# ZUM_Junior.net
KiCad netlist of a schematic drawn in Altium Designer
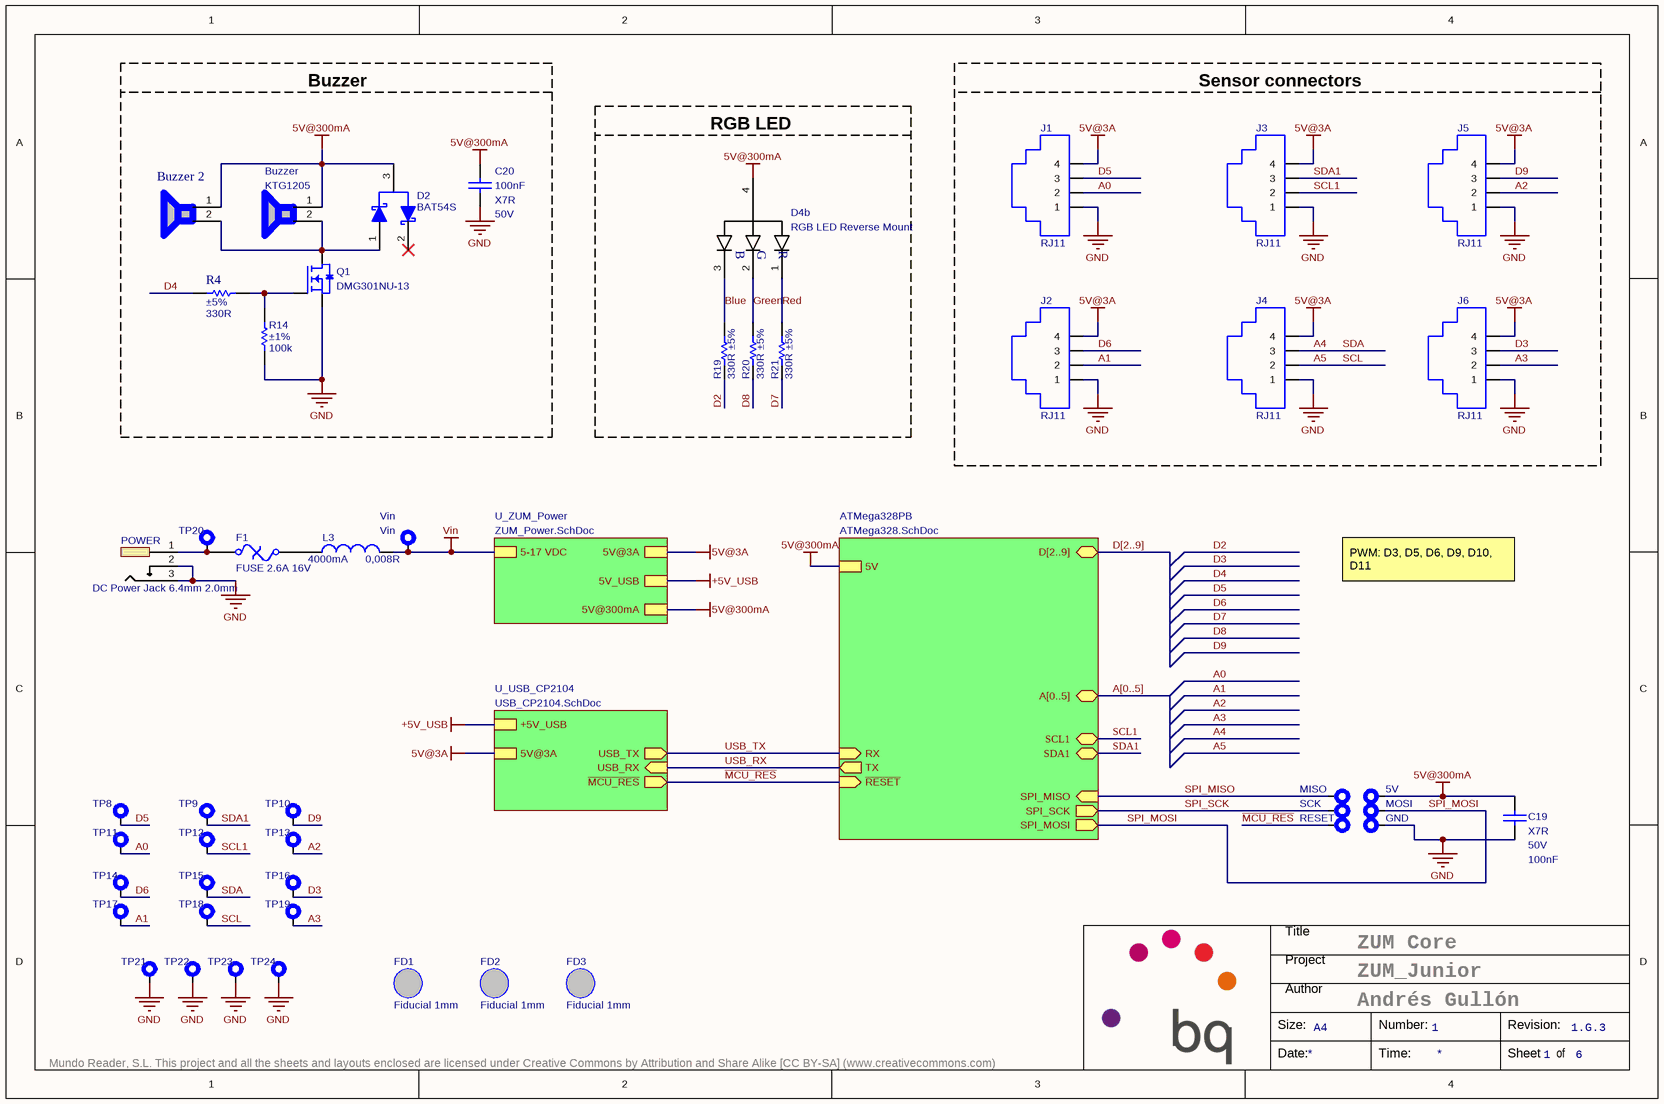
[diagram p0: ZUM_Junior.SchDoc]

(export (version "E")
  (design (tool "Eeschema 10.0.6"))
  (components
    (comp (ref "Buzzer")
      (value "KTG1205")
      (footprint "BUZZER SMD 13mm")
      (description "Buzzer")
      (fields (field (name "MANUFACTURER") "Kingstate Elect."))
      (libsource (lib "BQ Vault") (part "CMP-00356-1"))
    )
    (comp (ref "Buzzer 2")
      (value "Buzzer 8.5mm SMD")
      (footprint "YX-8014S05-2.7")
      (fields (field (name "MANUFACTURER") "Qinlon") (field (name "PART NUMBER") "YX-8014S-05"))
      (libsource (lib "BQ Vault") (part "BUZZER"))
    )
    (comp (ref "C19")
      (value "C0603_100nF_50V_±10%_X7R")
      (footprint "C0603")
      (fields
        (field (name "DIELECTRIC") "X7R")
        (field (name "VOLTAGE") "50V")
        (field (name "CAPACITANCE") "100nF")
        (field (name "MANUFACTURER") "Kemet")
        (field (name "TOLERANCE") "±10%")
      )
      (libsource (lib "BQ Vault") (part "CMP-00257-1"))
    )
    (comp (ref "C20")
      (value "C0603_100nF_50V_±10%_X7R")
      (footprint "C0603")
      (fields
        (field (name "DIELECTRIC") "X7R")
        (field (name "VOLTAGE") "50V")
        (field (name "CAPACITANCE") "100nF")
        (field (name "MANUFACTURER") "Kemet")
        (field (name "TOLERANCE") "±10%")
      )
      (libsource (lib "BQ Vault") (part "CMP-00257-1"))
    )
    (comp (ref "D2")
      (value "BAT54S")
      (footprint "SOT23-3")
      (description "Schottky Diode")
      (fields (field (name "MANUFACTURER") "NXP"))
      (libsource (lib "BQ Vault") (part "CMP-A2299-1"))
    )
    (comp (ref "D4b")
      (value "RGB LED Reverse Mount")
      (footprint "LED1205 Reverse")
      (fields (field (name "MANUFACTURER") "WÜrth Elektronik") (field (name "PART NUMBER") "RGB LED Reverse"))
      (libsource (lib "BQ Vault") (part "LED_RGB_2"))
    )
    (comp (ref "F1")
      (value "FUSE 2.6A 16V")
      (footprint "F1812")
      (description "Resettable Fuses")
      (fields (field (name "PART NUMBER") "FUSE 2.5A 16V") (field (name "VOLTAGE") "16V"))
      (libsource (lib "BQ Vault") (part "PTC_Fuse"))
    )
    (comp (ref "FD1")
      (value "Fiducial 1mm")
      (footprint "Fiducial_1mm")
      (description "Fiducial")
      (libsource (lib "BQ Vault") (part "Fiducial"))
    )
    (comp (ref "FD2")
      (value "Fiducial 1mm")
      (footprint "Fiducial_1mm")
      (description "Fiducial")
      (libsource (lib "BQ Vault") (part "Fiducial"))
    )
    (comp (ref "FD3")
      (value "Fiducial 1mm")
      (footprint "Fiducial_1mm")
      (description "Fiducial")
      (libsource (lib "BQ Vault") (part "Fiducial"))
    )
    (comp (ref "J1")
      (value "RJ11")
      (footprint "RJ11 SMD")
      (description "RJ11 4p4c SMD")
      (fields (field (name "MANUFACTURER") "Kycon"))
      (libsource (lib "BQ Vault") (part "RJ11"))
    )
    (comp (ref "J2")
      (value "RJ11")
      (footprint "RJ11 SMD")
      (description "RJ11 4p4c SMD")
      (fields (field (name "MANUFACTURER") "Kycon"))
      (libsource (lib "BQ Vault") (part "RJ11"))
    )
    (comp (ref "J3")
      (value "RJ11")
      (footprint "RJ11 SMD")
      (description "RJ11 4p4c SMD")
      (fields (field (name "MANUFACTURER") "Kycon"))
      (libsource (lib "BQ Vault") (part "RJ11"))
    )
    (comp (ref "J4")
      (value "RJ11")
      (footprint "RJ11 SMD")
      (description "RJ11 4p4c SMD")
      (fields (field (name "MANUFACTURER") "Kycon"))
      (libsource (lib "BQ Vault") (part "RJ11"))
    )
    (comp (ref "J5")
      (value "RJ11")
      (footprint "RJ11 SMD")
      (description "RJ11 4p4c SMD")
      (fields (field (name "MANUFACTURER") "Kycon"))
      (libsource (lib "BQ Vault") (part "RJ11"))
    )
    (comp (ref "J6")
      (value "RJ11")
      (footprint "RJ11 SMD")
      (description "RJ11 4p4c SMD")
      (fields (field (name "MANUFACTURER") "Kycon"))
      (libsource (lib "BQ Vault") (part "RJ11"))
    )
    (comp (ref "L3")
      (value "L0805_33R_0,008R_4000mA")
      (footprint "L0805")
      (fields
        (field (name "RESISTANCE_DC") "0,008R")
        (field (name "CURRENT") "4000mA")
        (field (name "MANUFACTURER") "Würth Elektronik")
      )
      (libsource (lib "BQ Vault") (part "CMP-A0714-1"))
    )
    (comp (ref "POWER")
      (value "DC Power Jack 6.4mm 2.0mm")
      (footprint "694106106102")
      (fields (field (name "MANUFACTURER") "Würth Elektronik") (field (name "PART NUMBER") "694106106102"))
      (libsource (lib "BQ Vault") (part "Power_Jack"))
    )
    (comp (ref "Q1")
      (value "DMG301NU-13")
      (footprint "SOT23-3")
      (description "N-MOSFET transistor")
      (fields (field (name "MANUFACTURER") "Diodes"))
      (libsource (lib "BQ Vault") (part "Mosfet_N"))
    )
    (comp (ref "R4")
      (value "R0402_330R_0.063W_±5%")
      (footprint "R0402")
      (fields
        (field (name "TOLERANCE") "±5%")
        (field (name "POWER") "0.063W")
        (field (name "RESISTANCE") "330R")
        (field (name "MANUFACTURER") "Vishay")
      )
      (libsource (lib "BQ Vault") (part "Resistor"))
    )
    (comp (ref "R14")
      (value "R0402_100k_0.063W_±1%")
      (footprint "R0402")
      (fields
        (field (name "TOLERANCE") "±1%")
        (field (name "POWER") "0.063W")
        (field (name "RESISTANCE") "100k")
        (field (name "MANUFACTURER") "Vishay")
      )
      (libsource (lib "BQ Vault") (part "CMP-A1835-2"))
    )
    (comp (ref "R19")
      (value "R0402_330R_0.063W_±5%")
      (footprint "R0402")
      (fields
        (field (name "TOLERANCE") "±5%")
        (field (name "POWER") "0.063W")
        (field (name "RESISTANCE") "330R")
        (field (name "MANUFACTURER") "Vishay")
      )
      (libsource (lib "BQ Vault") (part "Resistor"))
    )
    (comp (ref "R20")
      (value "R0402_330R_0.063W_±5%")
      (footprint "R0402")
      (fields
        (field (name "TOLERANCE") "±5%")
        (field (name "POWER") "0.063W")
        (field (name "RESISTANCE") "330R")
        (field (name "MANUFACTURER") "Vishay")
      )
      (libsource (lib "BQ Vault") (part "Resistor"))
    )
    (comp (ref "R21")
      (value "R0402_330R_0.063W_±5%")
      (footprint "R0402")
      (fields
        (field (name "TOLERANCE") "±5%")
        (field (name "POWER") "0.063W")
        (field (name "RESISTANCE") "330R")
        (field (name "MANUFACTURER") "Vishay")
      )
      (libsource (lib "BQ Vault") (part "Resistor"))
    )
    (comp (ref "TP8")
      (value "TP")
      (footprint "TP_POWER")
      (description "Testpoint 0.3mm")
      (fields (field (name "MANUFACTURER") "Oxley") (field (name "PART NUMBER") "TP_POWER"))
      (libsource (lib "BQ Vault") (part "CMP-A2499-3"))
    )
    (comp (ref "TP9")
      (value "TP")
      (footprint "TP_POWER")
      (description "Testpoint 0.3mm")
      (fields (field (name "MANUFACTURER") "Oxley") (field (name "PART NUMBER") "TP_POWER"))
      (libsource (lib "BQ Vault") (part "CMP-A2499-3"))
    )
    (comp (ref "TP10")
      (value "TP")
      (footprint "TP_POWER")
      (description "Testpoint 0.3mm")
      (fields (field (name "MANUFACTURER") "Oxley") (field (name "PART NUMBER") "TP_POWER"))
      (libsource (lib "BQ Vault") (part "CMP-A2499-3"))
    )
    (comp (ref "TP11")
      (value "TP")
      (footprint "TP_POWER")
      (description "Testpoint 0.3mm")
      (fields (field (name "MANUFACTURER") "Oxley") (field (name "PART NUMBER") "TP_POWER"))
      (libsource (lib "BQ Vault") (part "CMP-A2499-3"))
    )
    (comp (ref "TP12")
      (value "TP")
      (footprint "TP_POWER")
      (description "Testpoint 0.3mm")
      (fields (field (name "MANUFACTURER") "Oxley") (field (name "PART NUMBER") "TP_POWER"))
      (libsource (lib "BQ Vault") (part "CMP-A2499-3"))
    )
    (comp (ref "TP13")
      (value "TP")
      (footprint "TP_POWER")
      (description "Testpoint 0.3mm")
      (fields (field (name "MANUFACTURER") "Oxley") (field (name "PART NUMBER") "TP_POWER"))
      (libsource (lib "BQ Vault") (part "CMP-A2499-3"))
    )
    (comp (ref "TP14")
      (value "TP")
      (footprint "TP_POWER")
      (description "Testpoint 0.3mm")
      (fields (field (name "MANUFACTURER") "Oxley") (field (name "PART NUMBER") "TP_POWER"))
      (libsource (lib "BQ Vault") (part "CMP-A2499-3"))
    )
    (comp (ref "TP15")
      (value "TP")
      (footprint "TP_POWER")
      (description "Testpoint 0.3mm")
      (fields (field (name "MANUFACTURER") "Oxley") (field (name "PART NUMBER") "TP_POWER"))
      (libsource (lib "BQ Vault") (part "CMP-A2499-3"))
    )
    (comp (ref "TP16")
      (value "TP")
      (footprint "TP_POWER")
      (description "Testpoint 0.3mm")
      (fields (field (name "MANUFACTURER") "Oxley") (field (name "PART NUMBER") "TP_POWER"))
      (libsource (lib "BQ Vault") (part "CMP-A2499-3"))
    )
    (comp (ref "TP17")
      (value "TP")
      (footprint "TP_POWER")
      (description "Testpoint 0.3mm")
      (fields (field (name "MANUFACTURER") "Oxley") (field (name "PART NUMBER") "TP_POWER"))
      (libsource (lib "BQ Vault") (part "CMP-A2499-3"))
    )
    (comp (ref "TP18")
      (value "TP")
      (footprint "TP_POWER")
      (description "Testpoint 0.3mm")
      (fields (field (name "MANUFACTURER") "Oxley") (field (name "PART NUMBER") "TP_POWER"))
      (libsource (lib "BQ Vault") (part "CMP-A2499-3"))
    )
    (comp (ref "TP19")
      (value "TP")
      (footprint "TP_POWER")
      (description "Testpoint 0.3mm")
      (fields (field (name "MANUFACTURER") "Oxley") (field (name "PART NUMBER") "TP_POWER"))
      (libsource (lib "BQ Vault") (part "CMP-A2499-3"))
    )
    (comp (ref "TP20")
      (value "TP")
      (footprint "TP_POWER")
      (description "Testpoint 0.3mm")
      (fields (field (name "MANUFACTURER") "Oxley") (field (name "PART NUMBER") "TP_POWER"))
      (libsource (lib "BQ Vault") (part "CMP-A2499-3"))
    )
    (comp (ref "TP21")
      (value "TP")
      (footprint "TP_POWER")
      (description "Testpoint 0.3mm")
      (fields (field (name "MANUFACTURER") "Oxley") (field (name "PART NUMBER") "TP_POWER"))
      (libsource (lib "BQ Vault") (part "CMP-A2499-3"))
    )
    (comp (ref "TP22")
      (value "TP")
      (footprint "TP_POWER")
      (description "Testpoint 0.3mm")
      (fields (field (name "MANUFACTURER") "Oxley") (field (name "PART NUMBER") "TP_POWER"))
      (libsource (lib "BQ Vault") (part "CMP-A2499-3"))
    )
    (comp (ref "TP23")
      (value "TP")
      (footprint "TP_POWER")
      (description "Testpoint 0.3mm")
      (fields (field (name "MANUFACTURER") "Oxley") (field (name "PART NUMBER") "TP_POWER"))
      (libsource (lib "BQ Vault") (part "CMP-A2499-3"))
    )
    (comp (ref "TP24")
      (value "TP")
      (footprint "TP_POWER")
      (description "Testpoint 0.3mm")
      (fields (field (name "MANUFACTURER") "Oxley") (field (name "PART NUMBER") "TP_POWER"))
      (libsource (lib "BQ Vault") (part "CMP-A2499-3"))
    )
    (comp (ref "TP25")
      (value "MISO")
      (footprint "TP_POWER")
      (description "Testpoint 0.3mm")
      (fields (field (name "MANUFACTURER") "Oxley") (field (name "PART NUMBER") "TP_POWER"))
      (libsource (lib "BQ Vault") (part "CMP-A2499-3"))
    )
    (comp (ref "TP26")
      (value "5V")
      (footprint "TP_POWER")
      (description "Testpoint 0.3mm")
      (fields (field (name "MANUFACTURER") "Oxley") (field (name "PART NUMBER") "TP_POWER"))
      (libsource (lib "BQ Vault") (part "CMP-A2499-3"))
    )
    (comp (ref "TP27")
      (value "SCK")
      (footprint "TP_POWER")
      (description "Testpoint 0.3mm")
      (fields (field (name "MANUFACTURER") "Oxley") (field (name "PART NUMBER") "TP_POWER"))
      (libsource (lib "BQ Vault") (part "CMP-A2499-3"))
    )
    (comp (ref "TP28")
      (value "MOSI")
      (footprint "TP_POWER")
      (description "Testpoint 0.3mm")
      (fields (field (name "MANUFACTURER") "Oxley") (field (name "PART NUMBER") "TP_POWER"))
      (libsource (lib "BQ Vault") (part "CMP-A2499-3"))
    )
    (comp (ref "TP29")
      (value "GND")
      (footprint "TP_POWER")
      (description "Testpoint 0.3mm")
      (fields (field (name "MANUFACTURER") "Oxley") (field (name "PART NUMBER") "TP_POWER"))
      (libsource (lib "BQ Vault") (part "CMP-A2499-3"))
    )
    (comp (ref "TP30")
      (value "RESET")
      (footprint "TP_POWER")
      (description "Testpoint 0.3mm")
      (fields (field (name "MANUFACTURER") "Oxley") (field (name "PART NUMBER") "TP_POWER"))
      (libsource (lib "BQ Vault") (part "CMP-A2499-3"))
    )
    (comp (ref "Vin")
      (value "Vin")
      (footprint "TP_POWER")
      (description "Testpoint 0.3mm")
      (fields (field (name "MANUFACTURER") "Oxley") (field (name "PART NUMBER") "TP_POWER"))
      (libsource (lib "BQ Vault") (part "CMP-A2499-3"))
    )
  )
  (nets
    (net (code "2") (name "/A0") (class "Default")
      (node (ref "J1") (pin "2") (pinfunction "2_2") (pintype "passive"))
      (node (ref "TP11") (pin "1") (pinfunction "1_1") (pintype "passive"))
    )
    (net (code "3") (name "/A1") (class "Default")
      (node (ref "J2") (pin "2") (pinfunction "2_2") (pintype "passive"))
      (node (ref "TP17") (pin "1") (pinfunction "1_1") (pintype "passive"))
    )
    (net (code "4") (name "/A2") (class "Default")
      (node (ref "J5") (pin "2") (pinfunction "2_2") (pintype "passive"))
      (node (ref "TP13") (pin "1") (pinfunction "1_1") (pintype "passive"))
    )
    (net (code "5") (name "/A3") (class "Default")
      (node (ref "J6") (pin "2") (pinfunction "2_2") (pintype "passive"))
      (node (ref "TP19") (pin "1") (pinfunction "1_1") (pintype "passive"))
    )
    (net (code "6") (name "/A4") (class "Default")
      (node (ref "J4") (pin "3") (pinfunction "3_3") (pintype "passive"))
      (node (ref "TP15") (pin "1") (pinfunction "1_1") (pintype "passive"))
    )
    (net (code "7") (name "/A5") (class "Default")
      (node (ref "J4") (pin "2") (pinfunction "2_2") (pintype "passive"))
      (node (ref "TP18") (pin "1") (pinfunction "1_1") (pintype "passive"))
    )
    (net (code "9") (name "/Blue") (class "Default")
      (node (ref "D4b") (pin "3") (pinfunction "B_3") (pintype "power_in"))
      (node (ref "R19") (pin "2") (pinfunction "2_2") (pintype "passive"))
    )
    (net (code "10") (name "/D2") (class "Default")
      (node (ref "R19") (pin "1") (pinfunction "1_1") (pintype "passive"))
    )
    (net (code "11") (name "/D3") (class "Default")
      (node (ref "J6") (pin "3") (pinfunction "3_3") (pintype "passive"))
      (node (ref "TP16") (pin "1") (pinfunction "1_1") (pintype "passive"))
    )
    (net (code "12") (name "/D4") (class "Default")
      (node (ref "R4") (pin "1") (pinfunction "1_1") (pintype "passive"))
    )
    (net (code "13") (name "/D5") (class "Default")
      (node (ref "J1") (pin "3") (pinfunction "3_3") (pintype "passive"))
      (node (ref "TP8") (pin "1") (pinfunction "1_1") (pintype "passive"))
    )
    (net (code "14") (name "/D6") (class "Default")
      (node (ref "J2") (pin "3") (pinfunction "3_3") (pintype "passive"))
      (node (ref "TP14") (pin "1") (pinfunction "1_1") (pintype "passive"))
    )
    (net (code "15") (name "/D7") (class "Default")
      (node (ref "R21") (pin "1") (pinfunction "1_1") (pintype "passive"))
    )
    (net (code "16") (name "/D8") (class "Default")
      (node (ref "R20") (pin "1") (pinfunction "1_1") (pintype "passive"))
    )
    (net (code "17") (name "/D9") (class "Default")
      (node (ref "J5") (pin "3") (pinfunction "3_3") (pintype "passive"))
      (node (ref "TP10") (pin "1") (pinfunction "1_1") (pintype "passive"))
    )
    (net (code "19") (name "/Green") (class "Default")
      (node (ref "D4b") (pin "2") (pinfunction "R_2") (pintype "power_in"))
      (node (ref "R20") (pin "2") (pinfunction "2_2") (pintype "passive"))
    )
    (net (code "20") (name "/Red") (class "Default")
      (node (ref "D4b") (pin "1") (pinfunction "G_1") (pintype "power_in"))
      (node (ref "R21") (pin "2") (pinfunction "2_2") (pintype "passive"))
    )
    (net (code "21") (name "/SCL1") (class "Default")
      (node (ref "J3") (pin "2") (pinfunction "2_2") (pintype "passive"))
      (node (ref "TP12") (pin "1") (pinfunction "1_1") (pintype "passive"))
    )
    (net (code "22") (name "/SDA1") (class "Default")
      (node (ref "J3") (pin "3") (pinfunction "3_3") (pintype "passive"))
      (node (ref "TP9") (pin "1") (pinfunction "1_1") (pintype "passive"))
    )
    (net (code "23") (name "/SPI_MISO") (class "Default")
      (node (ref "TP25") (pin "1") (pinfunction "1_1") (pintype "passive"))
    )
    (net (code "24") (name "/SPI_MOSI") (class "Default")
      (node (ref "TP28") (pin "1") (pinfunction "1_1") (pintype "passive"))
    )
    (net (code "25") (name "/SPI_SCK") (class "Default")
      (node (ref "TP27") (pin "1") (pinfunction "1_1") (pintype "passive"))
    )
    (net (code "28") (name "/~{MCU_RES}") (class "Default")
      (node (ref "TP30") (pin "1") (pinfunction "1_1") (pintype "passive"))
    )
    (net (code "29") (name "5V@3A") (class "Default")
      (node (ref "J1") (pin "4") (pinfunction "4_4") (pintype "passive"))
      (node (ref "J2") (pin "4") (pinfunction "4_4") (pintype "passive"))
      (node (ref "J3") (pin "4") (pinfunction "4_4") (pintype "passive"))
      (node (ref "J4") (pin "4") (pinfunction "4_4") (pintype "passive"))
      (node (ref "J5") (pin "4") (pinfunction "4_4") (pintype "passive"))
      (node (ref "J6") (pin "4") (pinfunction "4_4") (pintype "passive"))
    )
    (net (code "30") (name "5V@300mA") (class "Default")
      (node (ref "Buzzer") (pin "1") (pinfunction "1_1") (pintype "passive"))
      (node (ref "Buzzer 2") (pin "1") (pinfunction "1_1") (pintype "passive"))
      (node (ref "C19") (pin "2") (pinfunction "2_2") (pintype "passive"))
      (node (ref "C20") (pin "2") (pinfunction "2_2") (pintype "passive"))
      (node (ref "D2") (pin "3") (pinfunction "K1_3") (pintype "passive"))
      (node (ref "D4b") (pin "4") (pinfunction "4_4") (pintype "power_in"))
      (node (ref "TP26") (pin "1") (pinfunction "1_1") (pintype "passive"))
    )
    (net (code "31") (name "GND") (class "Default")
      (node (ref "C19") (pin "1") (pinfunction "1_1") (pintype "passive"))
      (node (ref "C20") (pin "1") (pinfunction "1_1") (pintype "passive"))
      (node (ref "J1") (pin "1") (pinfunction "1_1") (pintype "passive"))
      (node (ref "J2") (pin "1") (pinfunction "1_1") (pintype "passive"))
      (node (ref "J3") (pin "1") (pinfunction "1_1") (pintype "passive"))
      (node (ref "J4") (pin "1") (pinfunction "1_1") (pintype "passive"))
      (node (ref "J5") (pin "1") (pinfunction "1_1") (pintype "passive"))
      (node (ref "J6") (pin "1") (pinfunction "1_1") (pintype "passive"))
      (node (ref "POWER") (pin "2") (pinfunction "2_2") (pintype "passive"))
      (node (ref "POWER") (pin "3") (pinfunction "3_3") (pintype "passive"))
      (node (ref "Q1") (pin "2") (pinfunction "S_2") (pintype "passive"))
      (node (ref "R14") (pin "1") (pinfunction "1_1") (pintype "passive"))
      (node (ref "TP21") (pin "1") (pinfunction "1_1") (pintype "passive"))
      (node (ref "TP22") (pin "1") (pinfunction "1_1") (pintype "passive"))
      (node (ref "TP23") (pin "1") (pinfunction "1_1") (pintype "passive"))
      (node (ref "TP24") (pin "1") (pinfunction "1_1") (pintype "passive"))
      (node (ref "TP29") (pin "1") (pinfunction "1_1") (pintype "passive"))
    )
    (net (code "32") (name "Net-(D2-A)") (class "Default")
      (node (ref "Buzzer") (pin "2") (pinfunction "2_2") (pintype "passive"))
      (node (ref "Buzzer 2") (pin "2") (pinfunction "2_2") (pintype "passive"))
      (node (ref "D2") (pin "1") (pinfunction "A_1") (pintype "passive"))
      (node (ref "Q1") (pin "3") (pinfunction "D_3") (pintype "passive"))
    )
    (net (code "33") (name "Net-(F1-Pad1)") (class "Default")
      (node (ref "F1") (pin "1") (pinfunction "1_1") (pintype "passive"))
      (node (ref "POWER") (pin "1") (pinfunction "1_1") (pintype "passive"))
      (node (ref "TP20") (pin "1") (pinfunction "1_1") (pintype "passive"))
    )
    (net (code "34") (name "Net-(F1-Pad2)") (class "Default")
      (node (ref "F1") (pin "2") (pinfunction "2_2") (pintype "passive"))
      (node (ref "L3") (pin "1") (pinfunction "1_1") (pintype "passive"))
    )
    (net (code "35") (name "Net-(Q1-G)") (class "Default")
      (node (ref "Q1") (pin "1") (pinfunction "G_1") (pintype "passive"))
      (node (ref "R14") (pin "2") (pinfunction "2_2") (pintype "passive"))
      (node (ref "R4") (pin "2") (pinfunction "2_2") (pintype "passive"))
    )
    (net (code "36") (name "Vin") (class "Default")
      (node (ref "L3") (pin "2") (pinfunction "2_2") (pintype "passive"))
      (node (ref "Vin") (pin "1") (pinfunction "1_1") (pintype "passive"))
    )
    (net (code "37") (name "unconnected-(D2-K2-Pad2)") (class "Default")
      (node (ref "D2") (pin "2") (pinfunction "K2_2") (pintype "passive+no_connect"))
    )
  )
)
